# TX5823_zmr250_2.net
KiCad netlist of a schematic drawn in EAGLE
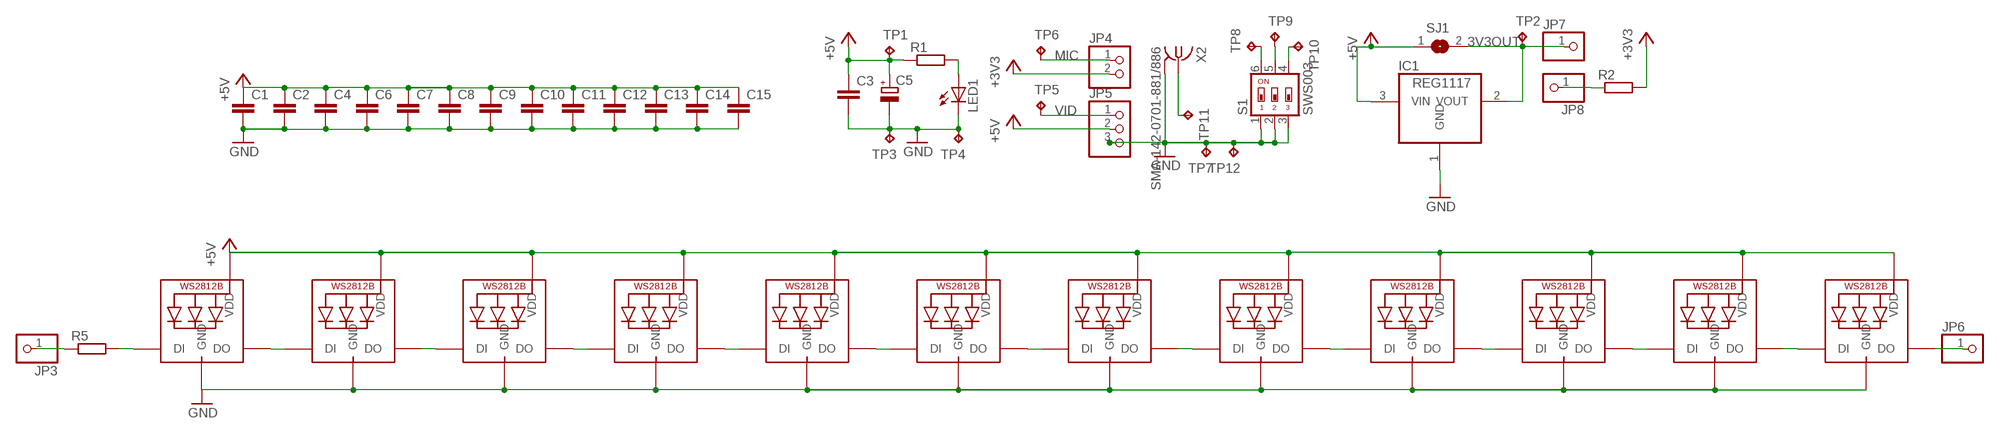
[diagram p0: schematic, sheet 1]

(export (version "E")
  (design (tool "Eeschema 10.0.6"))
  (components
    (comp (ref "C1")
      (value "C-EUC0603")
      (footprint "eagle-import:C0603")
      (libsource (lib "eagle-import") (part "C-EUC0603"))
    )
    (comp (ref "C2")
      (value "C-EUC0603")
      (footprint "eagle-import:C0603")
      (libsource (lib "eagle-import") (part "C-EUC0603"))
    )
    (comp (ref "C3")
      (value "C-EUC0805")
      (footprint "eagle-import:C0805")
      (libsource (lib "eagle-import") (part "C-EUC0805"))
    )
    (comp (ref "C4")
      (value "C-EUC0603")
      (footprint "eagle-import:C0603")
      (libsource (lib "eagle-import") (part "C-EUC0603"))
    )
    (comp (ref "C5")
      (value "CPOL-EUSMCB")
      (footprint "eagle-import:SMC_B")
      (libsource (lib "eagle-import") (part "CPOL-EUSMCB"))
    )
    (comp (ref "C6")
      (value "C-EUC0805")
      (footprint "eagle-import:C0805")
      (libsource (lib "eagle-import") (part "C-EUC0805"))
    )
    (comp (ref "C7")
      (value "C-EUC0603")
      (footprint "eagle-import:C0603")
      (libsource (lib "eagle-import") (part "C-EUC0603"))
    )
    (comp (ref "C8")
      (value "C-EUC0603")
      (footprint "eagle-import:C0603")
      (libsource (lib "eagle-import") (part "C-EUC0603"))
    )
    (comp (ref "C9")
      (value "C-EUC0805")
      (footprint "eagle-import:C0805")
      (libsource (lib "eagle-import") (part "C-EUC0805"))
    )
    (comp (ref "C10")
      (value "C-EUC0603")
      (footprint "eagle-import:C0603")
      (libsource (lib "eagle-import") (part "C-EUC0603"))
    )
    (comp (ref "C11")
      (value "C-EUC0603")
      (footprint "eagle-import:C0603")
      (libsource (lib "eagle-import") (part "C-EUC0603"))
    )
    (comp (ref "C12")
      (value "C-EUC0603")
      (footprint "eagle-import:C0603")
      (libsource (lib "eagle-import") (part "C-EUC0603"))
    )
    (comp (ref "C13")
      (value "C-EUC0805")
      (footprint "eagle-import:C0805")
      (libsource (lib "eagle-import") (part "C-EUC0805"))
    )
    (comp (ref "C14")
      (value "C-EUC0805")
      (footprint "eagle-import:C0805")
      (libsource (lib "eagle-import") (part "C-EUC0805"))
    )
    (comp (ref "C15")
      (value "C-EUC0805")
      (footprint "eagle-import:C0805")
      (libsource (lib "eagle-import") (part "C-EUC0805"))
    )
    (comp (ref "IC1")
      (value "REG1117")
      (footprint "eagle-import:SOT223")
      (libsource (lib "eagle-import") (part "REG1117"))
    )
    (comp (ref "JP3")
      (value "PINHD-1X1")
      (footprint "eagle-import:1X01")
      (libsource (lib "eagle-import") (part "PINHD-1X1"))
    )
    (comp (ref "JP4")
      (value "PINHD-1X2")
      (footprint "eagle-import:1X02")
      (libsource (lib "eagle-import") (part "PINHD-1X2"))
    )
    (comp (ref "JP5")
      (value "PINHD-1X3")
      (footprint "eagle-import:1X03")
      (libsource (lib "eagle-import") (part "PINHD-1X3"))
    )
    (comp (ref "JP6")
      (value "PINHD-1X1")
      (footprint "eagle-import:1X01")
      (libsource (lib "eagle-import") (part "PINHD-1X1"))
    )
    (comp (ref "JP7")
      (value "PINHD-1X1")
      (footprint "eagle-import:1X01")
      (libsource (lib "eagle-import") (part "PINHD-1X1"))
    )
    (comp (ref "JP8")
      (value "PINHD-1X1")
      (footprint "eagle-import:1X01")
      (libsource (lib "eagle-import") (part "PINHD-1X1"))
    )
    (comp (ref "LED1")
      (value "LEDCHIPLED_0603")
      (footprint "eagle-import:CHIPLED_0603")
      (libsource (lib "eagle-import") (part "LEDCHIPLED_0603"))
    )
    (comp (ref "LED2")
      (value "WS2812B5050")
      (footprint "eagle-import:WS2812B")
      (libsource (lib "eagle-import") (part "WS2812B5050"))
    )
    (comp (ref "LED3")
      (value "WS2812B5050")
      (footprint "eagle-import:WS2812B")
      (libsource (lib "eagle-import") (part "WS2812B5050"))
    )
    (comp (ref "LED4")
      (value "WS2812B5050")
      (footprint "eagle-import:WS2812B")
      (libsource (lib "eagle-import") (part "WS2812B5050"))
    )
    (comp (ref "LED5")
      (value "WS2812B5050")
      (footprint "eagle-import:WS2812B")
      (libsource (lib "eagle-import") (part "WS2812B5050"))
    )
    (comp (ref "LED6")
      (value "WS2812B5050")
      (footprint "eagle-import:WS2812B")
      (libsource (lib "eagle-import") (part "WS2812B5050"))
    )
    (comp (ref "LED7")
      (value "WS2812B5050")
      (footprint "eagle-import:WS2812B")
      (libsource (lib "eagle-import") (part "WS2812B5050"))
    )
    (comp (ref "LED8")
      (value "WS2812B5050")
      (footprint "eagle-import:WS2812B")
      (libsource (lib "eagle-import") (part "WS2812B5050"))
    )
    (comp (ref "LED9")
      (value "WS2812B5050")
      (footprint "eagle-import:WS2812B")
      (libsource (lib "eagle-import") (part "WS2812B5050"))
    )
    (comp (ref "LED10")
      (value "WS2812B5050")
      (footprint "eagle-import:WS2812B")
      (libsource (lib "eagle-import") (part "WS2812B5050"))
    )
    (comp (ref "LED11")
      (value "WS2812B5050")
      (footprint "eagle-import:WS2812B")
      (libsource (lib "eagle-import") (part "WS2812B5050"))
    )
    (comp (ref "LED12")
      (value "WS2812B5050")
      (footprint "eagle-import:WS2812B")
      (libsource (lib "eagle-import") (part "WS2812B5050"))
    )
    (comp (ref "LED13")
      (value "WS2812B5050")
      (footprint "eagle-import:WS2812B")
      (libsource (lib "eagle-import") (part "WS2812B5050"))
    )
    (comp (ref "R1")
      (value "R-EU_R0603")
      (footprint "eagle-import:R0603")
      (libsource (lib "eagle-import") (part "resistor_R-EU_R0603"))
    )
    (comp (ref "R2")
      (value "R-EU_M1406")
      (footprint "eagle-import:M1406")
      (libsource (lib "eagle-import") (part "R-EU_M1406"))
    )
    (comp (ref "R5")
      (value "R-EU_R0603")
      (footprint "eagle-import:R0603")
      (libsource (lib "eagle-import") (part "resistor_R-EU_R0603"))
    )
    (comp (ref "S1")
      (value "SWS003")
      (footprint "eagle-import:SMS-003")
      (libsource (lib "eagle-import") (part "SWS003"))
    )
    (comp (ref "SJ1") (value "SJ") (footprint "eagle-import:SJ") (libsource (lib "eagle-import") (part "SJ")))
    (comp (ref "TP1")
      (value "TPB1,27")
      (footprint "eagle-import:B1,27")
      (libsource (lib "eagle-import") (part "TPB1,27"))
    )
    (comp (ref "TP2")
      (value "TPB1,27")
      (footprint "eagle-import:B1,27")
      (libsource (lib "eagle-import") (part "TPB1,27"))
    )
    (comp (ref "TP3")
      (value "TPB1,27")
      (footprint "eagle-import:B1,27")
      (libsource (lib "eagle-import") (part "TPB1,27"))
    )
    (comp (ref "TP4")
      (value "TPB1,27")
      (footprint "eagle-import:B1,27")
      (libsource (lib "eagle-import") (part "TPB1,27"))
    )
    (comp (ref "TP5")
      (value "TPB1,27")
      (footprint "eagle-import:B1,27")
      (libsource (lib "eagle-import") (part "TPB1,27"))
    )
    (comp (ref "TP6")
      (value "TPB1,27")
      (footprint "eagle-import:B1,27")
      (libsource (lib "eagle-import") (part "TPB1,27"))
    )
    (comp (ref "TP7")
      (value "TPB1,27")
      (footprint "eagle-import:B1,27")
      (libsource (lib "eagle-import") (part "TPB1,27"))
    )
    (comp (ref "TP8")
      (value "TPB1,27")
      (footprint "eagle-import:B1,27")
      (libsource (lib "eagle-import") (part "TPB1,27"))
    )
    (comp (ref "TP9")
      (value "TPB1,27")
      (footprint "eagle-import:B1,27")
      (libsource (lib "eagle-import") (part "TPB1,27"))
    )
    (comp (ref "TP10")
      (value "TPB1,27")
      (footprint "eagle-import:B1,27")
      (libsource (lib "eagle-import") (part "TPB1,27"))
    )
    (comp (ref "TP11")
      (value "TPB1,27")
      (footprint "eagle-import:B1,27")
      (libsource (lib "eagle-import") (part "TPB1,27"))
    )
    (comp (ref "TP12")
      (value "TPB1,27")
      (footprint "eagle-import:B1,27")
      (libsource (lib "eagle-import") (part "TPB1,27"))
    )
    (comp (ref "X2")
      (value "SMA-142-0701-881/886")
      (footprint "eagle-import:J502-ND-142-0701-881_886")
      (fields (field (name "MF") "JOHNSON COMPONENTS") (field (name "MPN") "142-0701-881"))
      (libsource (lib "eagle-import") (part "SMA-142-0701-881/886"))
    )
  )
  (nets
    (net (code "1") (name "+3V3") (class "Default")
      (node (ref "JP4") (pin "2") (pinfunction "2_2") (pintype "passive"))
      (node (ref "R2") (pin "2") (pinfunction "2_2") (pintype "passive"))
    )
    (net (code "2") (name "+5V") (class "Default")
      (node (ref "C1") (pin "1") (pinfunction "1_1") (pintype "passive"))
      (node (ref "C10") (pin "1") (pinfunction "1_1") (pintype "passive"))
      (node (ref "C11") (pin "1") (pinfunction "1_1") (pintype "passive"))
      (node (ref "C12") (pin "1") (pinfunction "1_1") (pintype "passive"))
      (node (ref "C13") (pin "1") (pinfunction "1_1") (pintype "passive"))
      (node (ref "C14") (pin "1") (pinfunction "1_1") (pintype "passive"))
      (node (ref "C15") (pin "1") (pinfunction "1_1") (pintype "passive"))
      (node (ref "C2") (pin "1") (pinfunction "1_1") (pintype "passive"))
      (node (ref "C3") (pin "1") (pinfunction "1_1") (pintype "passive"))
      (node (ref "C4") (pin "1") (pinfunction "1_1") (pintype "passive"))
      (node (ref "C5") (pin "+") (pinfunction "+_+") (pintype "passive"))
      (node (ref "C6") (pin "1") (pinfunction "1_1") (pintype "passive"))
      (node (ref "C7") (pin "1") (pinfunction "1_1") (pintype "passive"))
      (node (ref "C8") (pin "1") (pinfunction "1_1") (pintype "passive"))
      (node (ref "C9") (pin "1") (pinfunction "1_1") (pintype "passive"))
      (node (ref "IC1") (pin "3") (pinfunction "VIN_3") (pintype "input"))
      (node (ref "JP5") (pin "2") (pinfunction "2_2") (pintype "passive"))
      (node (ref "LED10") (pin "1-VDD") (pinfunction "VDD_1-VDD") (pintype "power_in"))
      (node (ref "LED11") (pin "1-VDD") (pinfunction "VDD_1-VDD") (pintype "power_in"))
      (node (ref "LED12") (pin "1-VDD") (pinfunction "VDD_1-VDD") (pintype "power_in"))
      (node (ref "LED13") (pin "1-VDD") (pinfunction "VDD_1-VDD") (pintype "power_in"))
      (node (ref "LED2") (pin "1-VDD") (pinfunction "VDD_1-VDD") (pintype "power_in"))
      (node (ref "LED3") (pin "1-VDD") (pinfunction "VDD_1-VDD") (pintype "power_in"))
      (node (ref "LED4") (pin "1-VDD") (pinfunction "VDD_1-VDD") (pintype "power_in"))
      (node (ref "LED5") (pin "1-VDD") (pinfunction "VDD_1-VDD") (pintype "power_in"))
      (node (ref "LED6") (pin "1-VDD") (pinfunction "VDD_1-VDD") (pintype "power_in"))
      (node (ref "LED7") (pin "1-VDD") (pinfunction "VDD_1-VDD") (pintype "power_in"))
      (node (ref "LED8") (pin "1-VDD") (pinfunction "VDD_1-VDD") (pintype "power_in"))
      (node (ref "LED9") (pin "1-VDD") (pinfunction "VDD_1-VDD") (pintype "power_in"))
      (node (ref "R1") (pin "1") (pinfunction "1_1") (pintype "passive"))
      (node (ref "SJ1") (pin "1") (pinfunction "1_1") (pintype "passive"))
      (node (ref "TP1") (pin "TP") (pinfunction "TP_TP") (pintype "input"))
    )
    (net (code "3") (name "/3V3OUT") (class "Default")
      (node (ref "IC1") (pin "2") (pinfunction "VOUT_2") (pintype "output"))
      (node (ref "JP7") (pin "1") (pinfunction "1_1") (pintype "passive"))
      (node (ref "SJ1") (pin "2") (pinfunction "2_2") (pintype "passive"))
      (node (ref "TP2") (pin "TP") (pinfunction "TP_TP") (pintype "input"))
    )
    (net (code "4") (name "/MIC") (class "Default")
      (node (ref "JP4") (pin "1") (pinfunction "1_1") (pintype "passive"))
      (node (ref "TP6") (pin "TP") (pinfunction "TP_TP") (pintype "input"))
    )
    (net (code "5") (name "/VID") (class "Default")
      (node (ref "JP5") (pin "1") (pinfunction "1_1") (pintype "passive"))
      (node (ref "TP5") (pin "TP") (pinfunction "TP_TP") (pintype "input"))
    )
    (net (code "6") (name "GND") (class "Default")
      (node (ref "C1") (pin "2") (pinfunction "2_2") (pintype "passive"))
      (node (ref "C10") (pin "2") (pinfunction "2_2") (pintype "passive"))
      (node (ref "C11") (pin "2") (pinfunction "2_2") (pintype "passive"))
      (node (ref "C12") (pin "2") (pinfunction "2_2") (pintype "passive"))
      (node (ref "C13") (pin "2") (pinfunction "2_2") (pintype "passive"))
      (node (ref "C14") (pin "2") (pinfunction "2_2") (pintype "passive"))
      (node (ref "C15") (pin "2") (pinfunction "2_2") (pintype "passive"))
      (node (ref "C2") (pin "2") (pinfunction "2_2") (pintype "passive"))
      (node (ref "C3") (pin "2") (pinfunction "2_2") (pintype "passive"))
      (node (ref "C4") (pin "2") (pinfunction "2_2") (pintype "passive"))
      (node (ref "C5") (pin "-") (pinfunction "-_-") (pintype "passive"))
      (node (ref "C6") (pin "2") (pinfunction "2_2") (pintype "passive"))
      (node (ref "C7") (pin "2") (pinfunction "2_2") (pintype "passive"))
      (node (ref "C8") (pin "2") (pinfunction "2_2") (pintype "passive"))
      (node (ref "C9") (pin "2") (pinfunction "2_2") (pintype "passive"))
      (node (ref "IC1") (pin "1") (pinfunction "GND_1") (pintype "power_in"))
      (node (ref "JP5") (pin "3") (pinfunction "3_3") (pintype "passive"))
      (node (ref "LED1") (pin "C") (pinfunction "C_C") (pintype "passive"))
      (node (ref "LED10") (pin "3-GND") (pinfunction "GND_3-GND") (pintype "power_in"))
      (node (ref "LED11") (pin "3-GND") (pinfunction "GND_3-GND") (pintype "power_in"))
      (node (ref "LED12") (pin "3-GND") (pinfunction "GND_3-GND") (pintype "power_in"))
      (node (ref "LED13") (pin "3-GND") (pinfunction "GND_3-GND") (pintype "power_in"))
      (node (ref "LED2") (pin "3-GND") (pinfunction "GND_3-GND") (pintype "power_in"))
      (node (ref "LED3") (pin "3-GND") (pinfunction "GND_3-GND") (pintype "power_in"))
      (node (ref "LED4") (pin "3-GND") (pinfunction "GND_3-GND") (pintype "power_in"))
      (node (ref "LED5") (pin "3-GND") (pinfunction "GND_3-GND") (pintype "power_in"))
      (node (ref "LED6") (pin "3-GND") (pinfunction "GND_3-GND") (pintype "power_in"))
      (node (ref "LED7") (pin "3-GND") (pinfunction "GND_3-GND") (pintype "power_in"))
      (node (ref "LED8") (pin "3-GND") (pinfunction "GND_3-GND") (pintype "power_in"))
      (node (ref "LED9") (pin "3-GND") (pinfunction "GND_3-GND") (pintype "power_in"))
      (node (ref "S1") (pin "1") (pinfunction "1_1") (pintype "passive"))
      (node (ref "S1") (pin "2") (pinfunction "2_2") (pintype "passive"))
      (node (ref "S1") (pin "3") (pinfunction "3_3") (pintype "passive"))
      (node (ref "TP12") (pin "TP") (pinfunction "TP_TP") (pintype "input"))
      (node (ref "TP3") (pin "TP") (pinfunction "TP_TP") (pintype "input"))
      (node (ref "TP4") (pin "TP") (pinfunction "TP_TP") (pintype "input"))
      (node (ref "TP7") (pin "TP") (pinfunction "TP_TP") (pintype "input"))
      (node (ref "X2") (pin "G@1") (pinfunction "2_G@1") (pintype "passive"))
      (node (ref "X2") (pin "G@2") (pinfunction "2_G@2") (pintype "passive"))
      (node (ref "X2") (pin "G@3") (pinfunction "2_G@3") (pintype "passive"))
      (node (ref "X2") (pin "G@4") (pinfunction "2_G@4") (pintype "passive"))
    )
    (net (code "7") (name "Net-(JP3-Pad1)") (class "Default")
      (node (ref "JP3") (pin "1") (pinfunction "1_1") (pintype "passive"))
      (node (ref "R5") (pin "1") (pinfunction "1_1") (pintype "passive"))
    )
    (net (code "8") (name "Net-(JP8-Pad1)") (class "Default")
      (node (ref "JP8") (pin "1") (pinfunction "1_1") (pintype "passive"))
      (node (ref "R2") (pin "1") (pinfunction "1_1") (pintype "passive"))
    )
    (net (code "9") (name "Net-(LED1-PadA)") (class "Default")
      (node (ref "LED1") (pin "A") (pinfunction "A_A") (pintype "passive"))
      (node (ref "R1") (pin "2") (pinfunction "2_2") (pintype "passive"))
    )
    (net (code "10") (name "Net-(LED2-DI)") (class "Default")
      (node (ref "LED2") (pin "4-DIN") (pinfunction "DI_4-DIN") (pintype "input"))
      (node (ref "R5") (pin "2") (pinfunction "2_2") (pintype "passive"))
    )
    (net (code "11") (name "Net-(LED2-DO)") (class "Default")
      (node (ref "LED2") (pin "2-DOUT") (pinfunction "DO_2-DOUT") (pintype "output"))
      (node (ref "LED3") (pin "4-DIN") (pinfunction "DI_4-DIN") (pintype "input"))
    )
    (net (code "12") (name "Net-(LED3-DO)") (class "Default")
      (node (ref "LED3") (pin "2-DOUT") (pinfunction "DO_2-DOUT") (pintype "output"))
      (node (ref "LED4") (pin "4-DIN") (pinfunction "DI_4-DIN") (pintype "input"))
    )
    (net (code "13") (name "Net-(LED4-DO)") (class "Default")
      (node (ref "LED4") (pin "2-DOUT") (pinfunction "DO_2-DOUT") (pintype "output"))
      (node (ref "LED5") (pin "4-DIN") (pinfunction "DI_4-DIN") (pintype "input"))
    )
    (net (code "14") (name "Net-(LED5-DO)") (class "Default")
      (node (ref "LED5") (pin "2-DOUT") (pinfunction "DO_2-DOUT") (pintype "output"))
      (node (ref "LED6") (pin "4-DIN") (pinfunction "DI_4-DIN") (pintype "input"))
    )
    (net (code "15") (name "Net-(LED6-DO)") (class "Default")
      (node (ref "LED6") (pin "2-DOUT") (pinfunction "DO_2-DOUT") (pintype "output"))
      (node (ref "LED7") (pin "4-DIN") (pinfunction "DI_4-DIN") (pintype "input"))
    )
    (net (code "16") (name "Net-(LED7-DO)") (class "Default")
      (node (ref "LED7") (pin "2-DOUT") (pinfunction "DO_2-DOUT") (pintype "output"))
      (node (ref "LED9") (pin "4-DIN") (pinfunction "DI_4-DIN") (pintype "input"))
    )
    (net (code "17") (name "Net-(LED10-DI)") (class "Default")
      (node (ref "LED10") (pin "4-DIN") (pinfunction "DI_4-DIN") (pintype "input"))
      (node (ref "LED9") (pin "2-DOUT") (pinfunction "DO_2-DOUT") (pintype "output"))
    )
    (net (code "18") (name "Net-(LED10-DO)") (class "Default")
      (node (ref "LED10") (pin "2-DOUT") (pinfunction "DO_2-DOUT") (pintype "output"))
      (node (ref "LED8") (pin "4-DIN") (pinfunction "DI_4-DIN") (pintype "input"))
    )
    (net (code "19") (name "Net-(LED11-DI)") (class "Default")
      (node (ref "LED11") (pin "4-DIN") (pinfunction "DI_4-DIN") (pintype "input"))
      (node (ref "LED8") (pin "2-DOUT") (pinfunction "DO_2-DOUT") (pintype "output"))
    )
    (net (code "20") (name "Net-(LED11-DO)") (class "Default")
      (node (ref "LED11") (pin "2-DOUT") (pinfunction "DO_2-DOUT") (pintype "output"))
      (node (ref "LED12") (pin "4-DIN") (pinfunction "DI_4-DIN") (pintype "input"))
    )
    (net (code "21") (name "Net-(LED12-DO)") (class "Default")
      (node (ref "LED12") (pin "2-DOUT") (pinfunction "DO_2-DOUT") (pintype "output"))
      (node (ref "LED13") (pin "4-DIN") (pinfunction "DI_4-DIN") (pintype "input"))
    )
    (net (code "22") (name "Net-(LED13-DO)") (class "Default")
      (node (ref "JP6") (pin "1") (pinfunction "1_1") (pintype "passive"))
      (node (ref "LED13") (pin "2-DOUT") (pinfunction "DO_2-DOUT") (pintype "output"))
    )
    (net (code "23") (name "Net-(S1-Pad4)") (class "Default")
      (node (ref "S1") (pin "4") (pinfunction "4_4") (pintype "passive"))
      (node (ref "TP10") (pin "TP") (pinfunction "TP_TP") (pintype "input"))
    )
    (net (code "24") (name "Net-(S1-Pad5)") (class "Default")
      (node (ref "S1") (pin "5") (pinfunction "5_5") (pintype "passive"))
      (node (ref "TP9") (pin "TP") (pinfunction "TP_TP") (pintype "input"))
    )
    (net (code "25") (name "Net-(S1-Pad6)") (class "Default")
      (node (ref "S1") (pin "6") (pinfunction "6_6") (pintype "passive"))
      (node (ref "TP8") (pin "TP") (pinfunction "TP_TP") (pintype "input"))
    )
    (net (code "26") (name "Net-(TP11-PadTP)") (class "Default")
      (node (ref "TP11") (pin "TP") (pinfunction "TP_TP") (pintype "input"))
      (node (ref "X2") (pin "1") (pinfunction "1_1") (pintype "passive"))
    )
  )
)
